# 10_Ethernet-YT8521SC_CA.net
KiCad netlist of a schematic drawn in Altium Designer
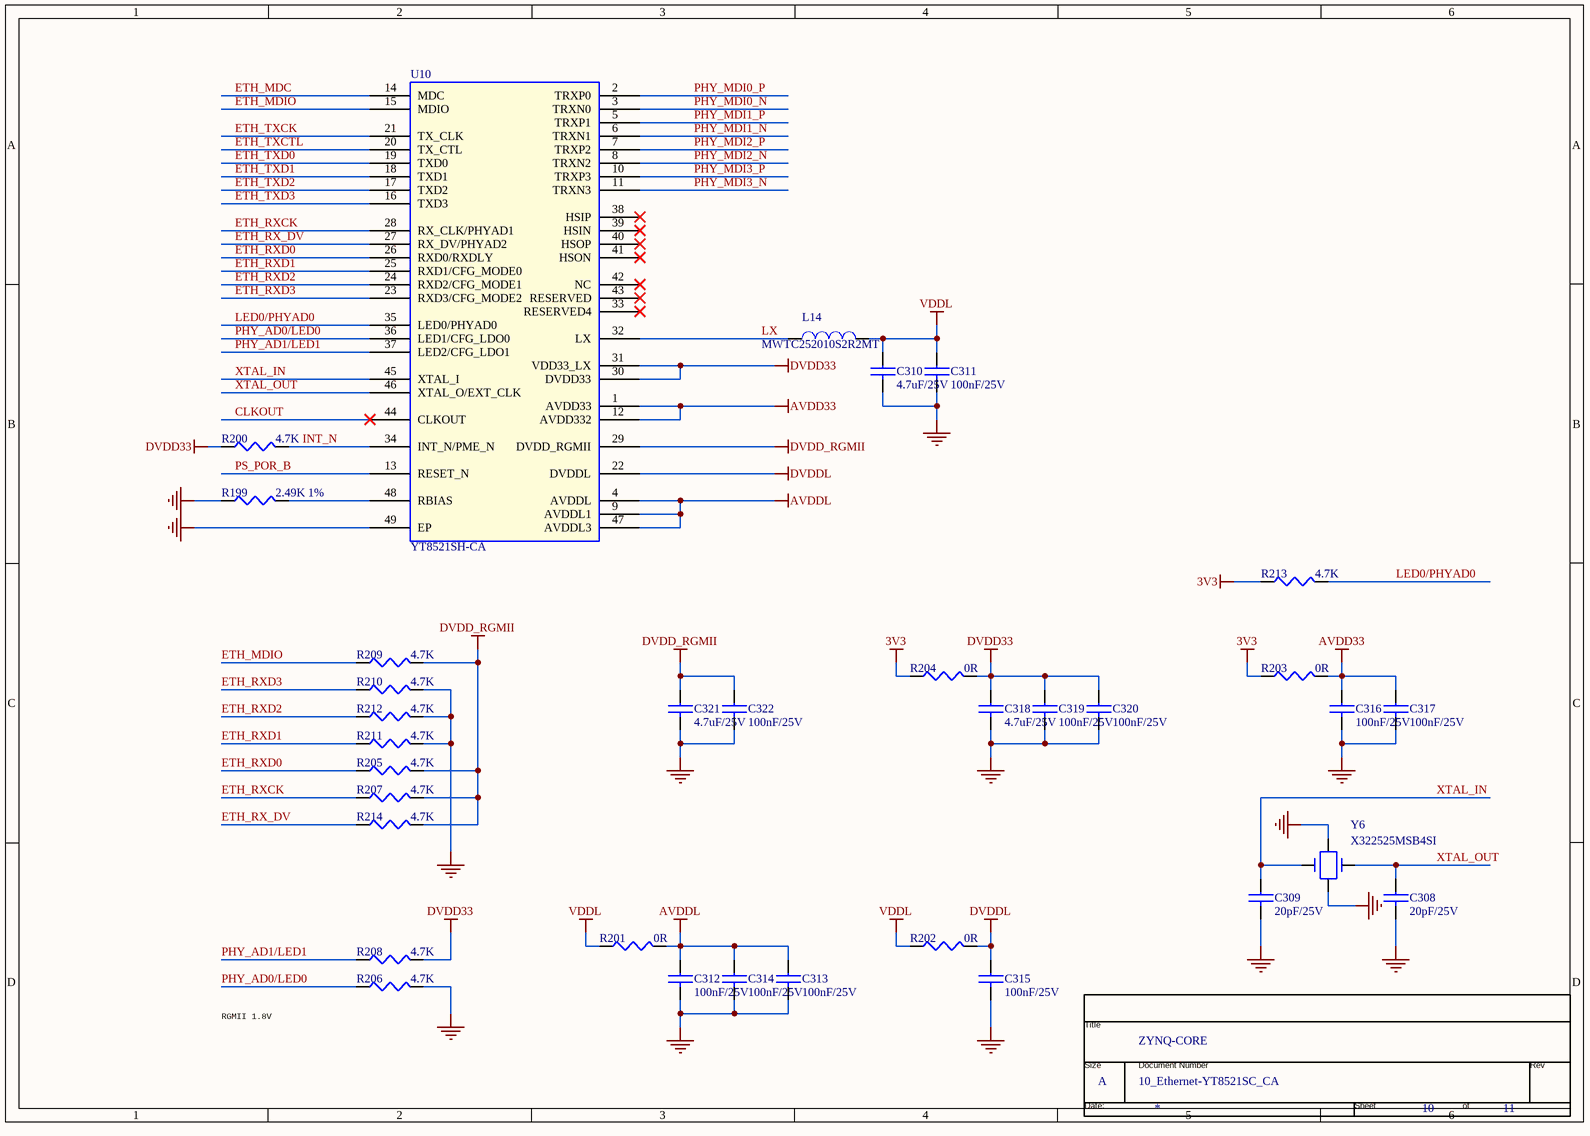
[diagram p0: 10_Ethernet-YT8521SC_CA.SchDoc]

(export (version "E")
  (design (tool "Eeschema 10.0.6"))
  (components
    (comp (ref "C308") (value "20pF/25V") (footprint "C0402") (libsource (lib "*") (part "CAP NP")))
    (comp (ref "C309") (value "20pF/25V") (footprint "C0402") (libsource (lib "*") (part "CAP NP")))
    (comp (ref "C310") (value "4.7uF/25V") (footprint "C0603") (libsource (lib "*") (part "CAP NP")))
    (comp (ref "C311") (value "100nF/25V") (footprint "C0402") (libsource (lib "*") (part "CAP NP")))
    (comp (ref "C312") (value "100nF/25V") (footprint "C0402") (libsource (lib "*") (part "CAP NP")))
    (comp (ref "C313") (value "100nF/25V") (footprint "C0402") (libsource (lib "*") (part "CAP NP")))
    (comp (ref "C314") (value "100nF/25V") (footprint "C0402") (libsource (lib "*") (part "CAP NP")))
    (comp (ref "C315") (value "100nF/25V") (footprint "C0402") (libsource (lib "*") (part "CAP NP")))
    (comp (ref "C316") (value "100nF/25V") (footprint "C0402") (libsource (lib "*") (part "CAP NP")))
    (comp (ref "C317") (value "100nF/25V") (footprint "C0402") (libsource (lib "*") (part "CAP NP")))
    (comp (ref "C318") (value "4.7uF/25V") (footprint "C0603") (libsource (lib "*") (part "CAP NP")))
    (comp (ref "C319") (value "100nF/25V") (footprint "C0402") (libsource (lib "*") (part "CAP NP")))
    (comp (ref "C320") (value "100nF/25V") (footprint "C0402") (libsource (lib "*") (part "CAP NP")))
    (comp (ref "C321") (value "4.7uF/25V") (footprint "C0603") (libsource (lib "*") (part "CAP NP")))
    (comp (ref "C322") (value "100nF/25V") (footprint "C0402") (libsource (lib "*") (part "CAP NP")))
    (comp (ref "L14") (value "MWTC252010S2R2MT") (footprint "2520") (libsource (lib "*") (part "INDUCTOR")))
    (comp (ref "R199") (value "2.49K 1%") (footprint "R0402") (libsource (lib "*") (part "RESISTOR_Dup1")))
    (comp (ref "R200") (value "4.7K") (footprint "R0402") (libsource (lib "*") (part "RESISTOR_Dup1")))
    (comp (ref "R201") (value "0R") (footprint "R0402") (libsource (lib "*") (part "RESISTOR_Dup1")))
    (comp (ref "R202") (value "0R") (footprint "R0402") (libsource (lib "*") (part "RESISTOR_Dup1")))
    (comp (ref "R203") (value "0R") (footprint "R0402") (libsource (lib "*") (part "RESISTOR_Dup1")))
    (comp (ref "R204") (value "0R") (footprint "R0402") (libsource (lib "*") (part "RESISTOR_Dup1")))
    (comp (ref "R205") (value "4.7K") (footprint "R0402") (libsource (lib "*") (part "RESISTOR_Dup1")))
    (comp (ref "R206") (value "4.7K") (footprint "R0402") (libsource (lib "*") (part "RESISTOR_Dup1")))
    (comp (ref "R207") (value "4.7K") (footprint "R0402") (libsource (lib "*") (part "RESISTOR_Dup1")))
    (comp (ref "R208") (value "4.7K") (footprint "R0402") (libsource (lib "*") (part "RESISTOR_Dup1")))
    (comp (ref "R209") (value "4.7K") (footprint "R0402") (libsource (lib "*") (part "RESISTOR_Dup1")))
    (comp (ref "R210") (value "4.7K") (footprint "R0402") (libsource (lib "*") (part "RESISTOR_Dup1")))
    (comp (ref "R211") (value "4.7K") (footprint "R0402") (libsource (lib "*") (part "RESISTOR_Dup1")))
    (comp (ref "R212") (value "4.7K") (footprint "R0402") (libsource (lib "*") (part "RESISTOR_Dup1")))
    (comp (ref "R213") (value "4.7K") (footprint "R0402") (libsource (lib "*") (part "RESISTOR_Dup1")))
    (comp (ref "R214") (value "4.7K") (footprint "R0402") (libsource (lib "*") (part "RESISTOR_Dup1")))
    (comp (ref "U10") (value "YT8521SH-CA") (footprint "QFN48") (libsource (lib "*") (part "YT8521S_1_U1_3")))
    (comp (ref "Y6")
      (value "X322525MSB4SI")
      (footprint "3225")
      (libsource (lib "*") (part "CRYSTAL_passive"))
    )
  )
  (nets
    (net (code "1") (name "/CLKOUT") (class "Default")
      (node (ref "U10") (pin "44") (pinfunction "CLKOUT_44") (pintype "passive+no_connect"))
    )
    (net (code "2") (name "/ETH_MDC") (class "Default")
      (node (ref "U10") (pin "14") (pinfunction "MDC_14") (pintype "passive"))
    )
    (net (code "3") (name "/ETH_MDIO") (class "Default")
      (node (ref "R209") (pin "1") (pinfunction "1_1") (pintype "passive"))
      (node (ref "U10") (pin "15") (pinfunction "MDIO_15") (pintype "passive"))
    )
    (net (code "4") (name "/ETH_RXCK") (class "Default")
      (node (ref "R207") (pin "1") (pinfunction "1_1") (pintype "passive"))
      (node (ref "U10") (pin "28") (pinfunction "RX_CLK/PHYAD1_28") (pintype "passive"))
    )
    (net (code "5") (name "/ETH_RXD0") (class "Default")
      (node (ref "R205") (pin "1") (pinfunction "1_1") (pintype "passive"))
      (node (ref "U10") (pin "26") (pinfunction "RXD0/RXDLY_26") (pintype "passive"))
    )
    (net (code "6") (name "/ETH_RXD1") (class "Default")
      (node (ref "R211") (pin "1") (pinfunction "1_1") (pintype "passive"))
      (node (ref "U10") (pin "25") (pinfunction "RXD1/CFG_MODE0_25") (pintype "passive"))
    )
    (net (code "7") (name "/ETH_RXD2") (class "Default")
      (node (ref "R212") (pin "1") (pinfunction "1_1") (pintype "passive"))
      (node (ref "U10") (pin "24") (pinfunction "RXD2/CFG_MODE1_24") (pintype "passive"))
    )
    (net (code "8") (name "/ETH_RXD3") (class "Default")
      (node (ref "R210") (pin "1") (pinfunction "1_1") (pintype "passive"))
      (node (ref "U10") (pin "23") (pinfunction "RXD3/CFG_MODE2_23") (pintype "passive"))
    )
    (net (code "9") (name "/ETH_RX_DV") (class "Default")
      (node (ref "R214") (pin "1") (pinfunction "1_1") (pintype "passive"))
      (node (ref "U10") (pin "27") (pinfunction "RX_DV/PHYAD2_27") (pintype "passive"))
    )
    (net (code "10") (name "/ETH_TXCK") (class "Default")
      (node (ref "U10") (pin "21") (pinfunction "TX_CLK_21") (pintype "passive"))
    )
    (net (code "11") (name "/ETH_TXCTL") (class "Default")
      (node (ref "U10") (pin "20") (pinfunction "TX_CTL_20") (pintype "passive"))
    )
    (net (code "12") (name "/ETH_TXD0") (class "Default")
      (node (ref "U10") (pin "19") (pinfunction "TXD0_19") (pintype "passive"))
    )
    (net (code "13") (name "/ETH_TXD1") (class "Default")
      (node (ref "U10") (pin "18") (pinfunction "TXD1_18") (pintype "passive"))
    )
    (net (code "14") (name "/ETH_TXD2") (class "Default")
      (node (ref "U10") (pin "17") (pinfunction "TXD2_17") (pintype "passive"))
    )
    (net (code "15") (name "/ETH_TXD3") (class "Default")
      (node (ref "U10") (pin "16") (pinfunction "TXD3_16") (pintype "passive"))
    )
    (net (code "16") (name "/INT_N") (class "Default")
      (node (ref "R200") (pin "2") (pinfunction "2_2") (pintype "passive"))
      (node (ref "U10") (pin "34") (pinfunction "INT_N/PME_N_34") (pintype "passive"))
    )
    (net (code "17") (name "/LED0{slash}PHYAD0") (class "Default")
      (node (ref "R213") (pin "2") (pinfunction "2_2") (pintype "passive"))
      (node (ref "U10") (pin "35") (pinfunction "LED0/PHYAD0_35") (pintype "passive"))
    )
    (net (code "18") (name "/LX") (class "Default")
      (node (ref "L14") (pin "1") (pinfunction "1_1") (pintype "passive"))
      (node (ref "U10") (pin "32") (pinfunction "LX_32") (pintype "power_in"))
    )
    (net (code "19") (name "/PHY_AD0{slash}LED0") (class "Default")
      (node (ref "R206") (pin "1") (pinfunction "1_1") (pintype "passive"))
      (node (ref "U10") (pin "36") (pinfunction "LED1/CFG_LDO0_36") (pintype "passive"))
    )
    (net (code "20") (name "/PHY_AD1{slash}LED1") (class "Default")
      (node (ref "R208") (pin "1") (pinfunction "1_1") (pintype "passive"))
      (node (ref "U10") (pin "37") (pinfunction "LED2/CFG_LDO1_37") (pintype "passive"))
    )
    (net (code "21") (name "/PHY_MDI0_N") (class "Default")
      (node (ref "U10") (pin "3") (pinfunction "TRXN0_3") (pintype "passive"))
    )
    (net (code "22") (name "/PHY_MDI0_P") (class "Default")
      (node (ref "U10") (pin "2") (pinfunction "TRXP0_2") (pintype "passive"))
    )
    (net (code "23") (name "/PHY_MDI1_N") (class "Default")
      (node (ref "U10") (pin "6") (pinfunction "TRXN1_6") (pintype "passive"))
    )
    (net (code "24") (name "/PHY_MDI1_P") (class "Default")
      (node (ref "U10") (pin "5") (pinfunction "TRXP1_5") (pintype "passive"))
    )
    (net (code "25") (name "/PHY_MDI2_N") (class "Default")
      (node (ref "U10") (pin "8") (pinfunction "TRXN2_8") (pintype "passive"))
    )
    (net (code "26") (name "/PHY_MDI2_P") (class "Default")
      (node (ref "U10") (pin "7") (pinfunction "TRXP2_7") (pintype "passive"))
    )
    (net (code "27") (name "/PHY_MDI3_N") (class "Default")
      (node (ref "U10") (pin "11") (pinfunction "TRXN3_11") (pintype "passive"))
    )
    (net (code "28") (name "/PHY_MDI3_P") (class "Default")
      (node (ref "U10") (pin "10") (pinfunction "TRXP3_10") (pintype "passive"))
    )
    (net (code "29") (name "/PS_POR_B") (class "Default")
      (node (ref "U10") (pin "13") (pinfunction "RESET_N_13") (pintype "passive"))
    )
    (net (code "30") (name "/XTAL_IN") (class "Default")
      (node (ref "C309") (pin "1") (pinfunction "1_1") (pintype "passive"))
      (node (ref "U10") (pin "45") (pinfunction "XTAL_I_45") (pintype "passive"))
      (node (ref "Y6") (pin "3") (pinfunction "3_3") (pintype "passive"))
    )
    (net (code "31") (name "/XTAL_OUT") (class "Default")
      (node (ref "C308") (pin "1") (pinfunction "1_1") (pintype "passive"))
      (node (ref "U10") (pin "46") (pinfunction "XTAL_O/EXT_CLK_46") (pintype "passive"))
      (node (ref "Y6") (pin "1") (pinfunction "1_1") (pintype "passive"))
    )
    (net (code "32") (name "3V3") (class "Default")
      (node (ref "R203") (pin "1") (pinfunction "1_1") (pintype "passive"))
      (node (ref "R204") (pin "1") (pinfunction "1_1") (pintype "passive"))
      (node (ref "R213") (pin "1") (pinfunction "1_1") (pintype "passive"))
    )
    (net (code "33") (name "AVDD33") (class "Default")
      (node (ref "C316") (pin "1") (pinfunction "1_1") (pintype "passive"))
      (node (ref "C317") (pin "1") (pinfunction "1_1") (pintype "passive"))
      (node (ref "R203") (pin "2") (pinfunction "2_2") (pintype "passive"))
      (node (ref "U10") (pin "1") (pinfunction "AVDD33_1") (pintype "passive"))
      (node (ref "U10") (pin "12") (pinfunction "AVDD332_12") (pintype "passive"))
    )
    (net (code "34") (name "AVDDL") (class "Default")
      (node (ref "C312") (pin "1") (pinfunction "1_1") (pintype "passive"))
      (node (ref "C313") (pin "1") (pinfunction "1_1") (pintype "passive"))
      (node (ref "C314") (pin "1") (pinfunction "1_1") (pintype "passive"))
      (node (ref "R201") (pin "2") (pinfunction "2_2") (pintype "passive"))
      (node (ref "U10") (pin "4") (pinfunction "AVDDL_4") (pintype "passive"))
      (node (ref "U10") (pin "47") (pinfunction "AVDDL3_47") (pintype "passive"))
      (node (ref "U10") (pin "9") (pinfunction "AVDDL1_9") (pintype "passive"))
    )
    (net (code "35") (name "DVDD33") (class "Default")
      (node (ref "C318") (pin "1") (pinfunction "1_1") (pintype "passive"))
      (node (ref "C319") (pin "1") (pinfunction "1_1") (pintype "passive"))
      (node (ref "C320") (pin "1") (pinfunction "1_1") (pintype "passive"))
      (node (ref "R200") (pin "1") (pinfunction "1_1") (pintype "passive"))
      (node (ref "R204") (pin "2") (pinfunction "2_2") (pintype "passive"))
      (node (ref "R208") (pin "2") (pinfunction "2_2") (pintype "passive"))
      (node (ref "U10") (pin "30") (pinfunction "DVDD33_30") (pintype "passive"))
      (node (ref "U10") (pin "31") (pinfunction "VDD33_LX_31") (pintype "passive"))
    )
    (net (code "36") (name "DVDDL") (class "Default")
      (node (ref "C315") (pin "1") (pinfunction "1_1") (pintype "passive"))
      (node (ref "R202") (pin "2") (pinfunction "2_2") (pintype "passive"))
      (node (ref "U10") (pin "22") (pinfunction "DVDDL_22") (pintype "passive"))
    )
    (net (code "37") (name "DVDD_RGMII") (class "Default")
      (node (ref "C321") (pin "1") (pinfunction "1_1") (pintype "passive"))
      (node (ref "C322") (pin "1") (pinfunction "1_1") (pintype "passive"))
      (node (ref "R205") (pin "2") (pinfunction "2_2") (pintype "passive"))
      (node (ref "R207") (pin "2") (pinfunction "2_2") (pintype "passive"))
      (node (ref "R209") (pin "2") (pinfunction "2_2") (pintype "passive"))
      (node (ref "R214") (pin "2") (pinfunction "2_2") (pintype "passive"))
      (node (ref "U10") (pin "29") (pinfunction "DVDD_RGMII_29") (pintype "passive"))
    )
    (net (code "38") (name "GND") (class "Default")
      (node (ref "C308") (pin "2") (pinfunction "2_2") (pintype "passive"))
      (node (ref "C309") (pin "2") (pinfunction "2_2") (pintype "passive"))
      (node (ref "C310") (pin "2") (pinfunction "2_2") (pintype "passive"))
      (node (ref "C311") (pin "2") (pinfunction "2_2") (pintype "passive"))
      (node (ref "C312") (pin "2") (pinfunction "2_2") (pintype "passive"))
      (node (ref "C313") (pin "2") (pinfunction "2_2") (pintype "passive"))
      (node (ref "C314") (pin "2") (pinfunction "2_2") (pintype "passive"))
      (node (ref "C315") (pin "2") (pinfunction "2_2") (pintype "passive"))
      (node (ref "C316") (pin "2") (pinfunction "2_2") (pintype "passive"))
      (node (ref "C317") (pin "2") (pinfunction "2_2") (pintype "passive"))
      (node (ref "C318") (pin "2") (pinfunction "2_2") (pintype "passive"))
      (node (ref "C319") (pin "2") (pinfunction "2_2") (pintype "passive"))
      (node (ref "C320") (pin "2") (pinfunction "2_2") (pintype "passive"))
      (node (ref "C321") (pin "2") (pinfunction "2_2") (pintype "passive"))
      (node (ref "C322") (pin "2") (pinfunction "2_2") (pintype "passive"))
      (node (ref "R199") (pin "1") (pinfunction "1_1") (pintype "passive"))
      (node (ref "R206") (pin "2") (pinfunction "2_2") (pintype "passive"))
      (node (ref "R210") (pin "2") (pinfunction "2_2") (pintype "passive"))
      (node (ref "R211") (pin "2") (pinfunction "2_2") (pintype "passive"))
      (node (ref "R212") (pin "2") (pinfunction "2_2") (pintype "passive"))
      (node (ref "U10") (pin "49") (pinfunction "EP_49") (pintype "passive"))
      (node (ref "Y6") (pin "2") (pinfunction "2_2") (pintype "passive"))
      (node (ref "Y6") (pin "4") (pinfunction "4_4") (pintype "passive"))
    )
    (net (code "39") (name "Net-(U10-RBIAS)") (class "Default")
      (node (ref "R199") (pin "2") (pinfunction "2_2") (pintype "passive"))
      (node (ref "U10") (pin "48") (pinfunction "RBIAS_48") (pintype "passive"))
    )
    (net (code "40") (name "VDDL") (class "Default")
      (node (ref "C310") (pin "1") (pinfunction "1_1") (pintype "passive"))
      (node (ref "C311") (pin "1") (pinfunction "1_1") (pintype "passive"))
      (node (ref "L14") (pin "2") (pinfunction "2_2") (pintype "passive"))
      (node (ref "R201") (pin "1") (pinfunction "1_1") (pintype "passive"))
      (node (ref "R202") (pin "1") (pinfunction "1_1") (pintype "passive"))
    )
    (net (code "41") (name "unconnected-(U10-HSIN-Pad39)") (class "Default")
      (node (ref "U10") (pin "39") (pinfunction "HSIN_39") (pintype "passive+no_connect"))
    )
    (net (code "42") (name "unconnected-(U10-HSIP-Pad38)") (class "Default")
      (node (ref "U10") (pin "38") (pinfunction "HSIP_38") (pintype "passive+no_connect"))
    )
    (net (code "43") (name "unconnected-(U10-HSON-Pad41)") (class "Default")
      (node (ref "U10") (pin "41") (pinfunction "HSON_41") (pintype "passive+no_connect"))
    )
    (net (code "44") (name "unconnected-(U10-HSOP-Pad40)") (class "Default")
      (node (ref "U10") (pin "40") (pinfunction "HSOP_40") (pintype "passive+no_connect"))
    )
    (net (code "45") (name "unconnected-(U10-NC-Pad42)") (class "Default")
      (node (ref "U10") (pin "42") (pinfunction "NC_42") (pintype "passive+no_connect"))
    )
    (net (code "46") (name "unconnected-(U10-RESERVED-Pad43)") (class "Default")
      (node (ref "U10") (pin "43") (pinfunction "RESERVED_43") (pintype "passive+no_connect"))
    )
    (net (code "47") (name "unconnected-(U10-RESERVED4-Pad33)") (class "Default")
      (node (ref "U10") (pin "33") (pinfunction "RESERVED4_33") (pintype "passive+no_connect"))
    )
  )
)
